# microGate.net
KiCad netlist of a schematic drawn in Altium Designer
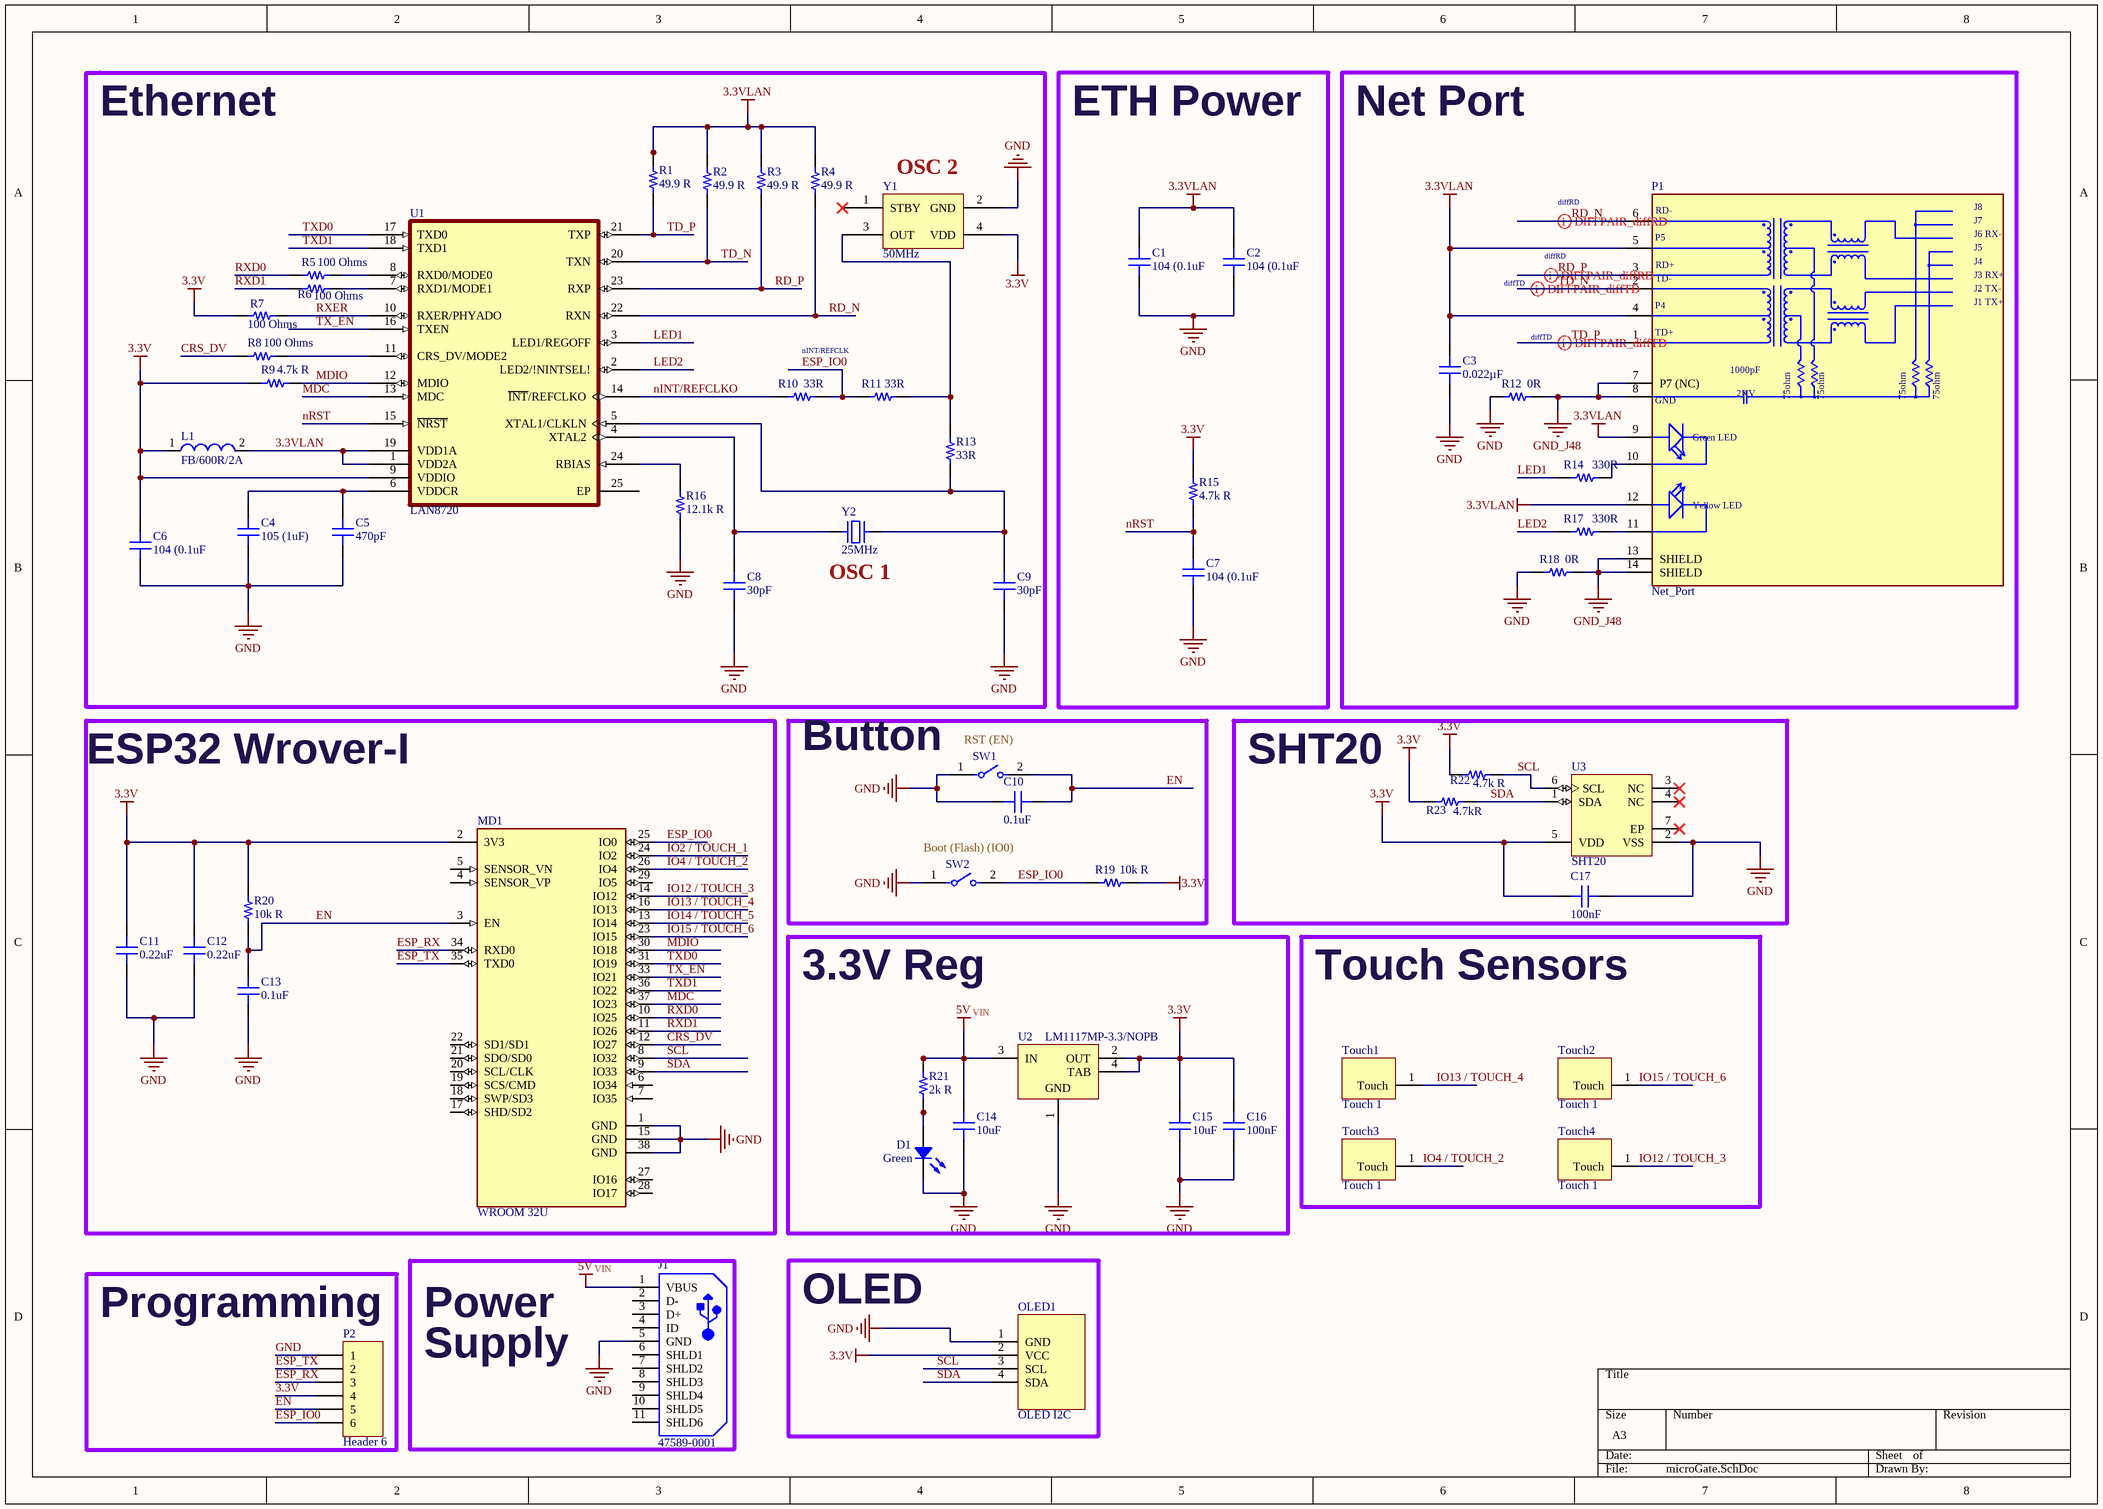
[diagram p0: microGate.SchDoc]

(export (version "E")
  (design (tool "Eeschema 10.0.6"))
  (components
    (comp (ref "C1")
      (value "104 (0.1uF")
      (footprint "CAP 0805_2012")
      (description "CAP CER SMD 0805 22PF 5% 50V X7R")
      (fields (field (name "PART NUMBER") "C0805C220J5RAC7800") (field (name "MANUFACTURER") "KEMET"))
      (libsource (lib "Celestial Altium Library - altium_library") (part "Capacitor"))
    )
    (comp (ref "C2")
      (value "104 (0.1uF")
      (footprint "CAP 0805_2012")
      (description "CAP CER SMD 0805 22PF 5% 50V X7R")
      (fields (field (name "PART NUMBER") "C0805C220J5RAC7800") (field (name "MANUFACTURER") "KEMET"))
      (libsource (lib "Celestial Altium Library - altium_library") (part "Capacitor"))
    )
    (comp (ref "C3")
      (value "0.022µF")
      (footprint "CAP 0805_2012")
      (description "CAP CER SMD 0805 22PF 5% 50V X7R")
      (fields (field (name "PART NUMBER") "C0805C220J5RAC7800") (field (name "MANUFACTURER") "KEMET"))
      (libsource (lib "Celestial Altium Library - altium_library") (part "Capacitor"))
    )
    (comp (ref "C4")
      (value "105 (1uF)")
      (footprint "CAP 0805_2012")
      (description "CAP CER SMD 0805 22PF 5% 50V X7R")
      (fields (field (name "PART NUMBER") "C0805C220J5RAC7800") (field (name "MANUFACTURER") "KEMET"))
      (libsource (lib "Celestial Altium Library - altium_library") (part "Capacitor"))
    )
    (comp (ref "C5")
      (value "470pF")
      (footprint "CAP 0805_2012")
      (description "CAP CER SMD 0805 22PF 5% 50V X7R")
      (fields (field (name "PART NUMBER") "C0805C220J5RAC7800") (field (name "MANUFACTURER") "KEMET"))
      (libsource (lib "Celestial Altium Library - altium_library") (part "Capacitor"))
    )
    (comp (ref "C6")
      (value "104 (0.1uF")
      (footprint "CAP 0805_2012")
      (description "CAP CER SMD 0805 22PF 5% 50V X7R")
      (fields (field (name "PART NUMBER") "C0805C220J5RAC7800") (field (name "MANUFACTURER") "KEMET"))
      (libsource (lib "Celestial Altium Library - altium_library") (part "Capacitor"))
    )
    (comp (ref "C7")
      (value "104 (0.1uF")
      (footprint "CAP 0805_2012")
      (description "CAP CER SMD 0805 22PF 5% 50V X7R")
      (fields (field (name "PART NUMBER") "C0805C220J5RAC7800") (field (name "MANUFACTURER") "KEMET"))
      (libsource (lib "Celestial Altium Library - altium_library") (part "Capacitor"))
    )
    (comp (ref "C8")
      (value "30pF")
      (footprint "CAP 0805_2012")
      (description "CAP CER SMD 0805 22PF 5% 50V X7R")
      (fields (field (name "PART NUMBER") "C0805C220J5RAC7800") (field (name "MANUFACTURER") "KEMET"))
      (libsource (lib "Celestial Altium Library - altium_library") (part "Capacitor"))
    )
    (comp (ref "C9")
      (value "30pF")
      (footprint "CAP 0805_2012")
      (description "CAP CER SMD 0805 22PF 5% 50V X7R")
      (fields (field (name "PART NUMBER") "C0805C220J5RAC7800") (field (name "MANUFACTURER") "KEMET"))
      (libsource (lib "Celestial Altium Library - altium_library") (part "Capacitor"))
    )
    (comp (ref "C10")
      (value "0.1uF")
      (footprint "CAP 0805_2012")
      (description "CAP CER SMD 0805 22PF 5% 50V X7R")
      (fields (field (name "PART NUMBER") "C0805C220J5RAC7800") (field (name "MANUFACTURER") "KEMET"))
      (libsource (lib "Celestial Altium Library - altium_library") (part "Capacitor"))
    )
    (comp (ref "C11")
      (value "0.22uF")
      (footprint "CAP 0805_2012")
      (description "CAP CER SMD 0805 22PF 5% 50V X7R")
      (fields (field (name "PART NUMBER") "C0805C220J5RAC7800") (field (name "MANUFACTURER") "KEMET"))
      (libsource (lib "Celestial Altium Library - altium_library") (part "Capacitor"))
    )
    (comp (ref "C12")
      (value "0.22uF")
      (footprint "CAP 0805_2012")
      (description "CAP CER SMD 0805 22PF 5% 50V X7R")
      (fields (field (name "PART NUMBER") "C0805C220J5RAC7800") (field (name "MANUFACTURER") "KEMET"))
      (libsource (lib "Celestial Altium Library - altium_library") (part "Capacitor"))
    )
    (comp (ref "C13")
      (value "0.1uF")
      (footprint "CAP 0805_2012")
      (description "CAP CER SMD 0805 22PF 5% 50V X7R")
      (fields (field (name "PART NUMBER") "C0805C220J5RAC7800") (field (name "MANUFACTURER") "KEMET"))
      (libsource (lib "Celestial Altium Library - altium_library") (part "Capacitor"))
    )
    (comp (ref "C14")
      (value "10uF")
      (footprint "CAP 0805_2012")
      (description "CAP CER SMD 0805 22PF 5% 50V X7R")
      (fields (field (name "PART NUMBER") "C0805C220J5RAC7800") (field (name "MANUFACTURER") "KEMET"))
      (libsource (lib "Celestial Altium Library - altium_library") (part "Capacitor"))
    )
    (comp (ref "C15")
      (value "10uF")
      (footprint "CAP 0805_2012")
      (description "CAP CER SMD 0805 22PF 5% 50V X7R")
      (fields (field (name "PART NUMBER") "C0805C220J5RAC7800") (field (name "MANUFACTURER") "KEMET"))
      (libsource (lib "Celestial Altium Library - altium_library") (part "Capacitor"))
    )
    (comp (ref "C16")
      (value "100nF")
      (footprint "CAP 0805_2012")
      (description "CAP CER SMD 0805 22PF 5% 50V X7R")
      (fields (field (name "PART NUMBER") "C0805C220J5RAC7800") (field (name "MANUFACTURER") "KEMET"))
      (libsource (lib "Celestial Altium Library - altium_library") (part "Capacitor"))
    )
    (comp (ref "C17")
      (value "100nF")
      (footprint "CAP 0805_2012")
      (description "CAP CER SMD 0805 22PF 5% 50V X7R")
      (fields (field (name "PART NUMBER") "C0805C220J5RAC7800") (field (name "MANUFACTURER") "KEMET"))
      (libsource (lib "Celestial Altium Library - altium_library") (part "Capacitor"))
    )
    (comp (ref "D1")
      (value "Green")
      (footprint "LED 0603_1608 GREEN")
      (description "LED GREEN DIFFUSED 1608 SMD")
      (fields (field (name "PART NUMBER") "BG1111C-TR") (field (name "MANUFACTURER") "Stanley Electric Co"))
      (libsource (lib "Celestial Altium Library - altium_library") (part "LED"))
    )
    (comp (ref "J1")
      (value "47589-0001")
      (footprint "MOLX-47589-0001_V")
      (description "Right Angle Female Type AB Micro USB Connector, 30 V, 1.8 A, -30 to 85 degC, RoHS, Tape and Reel")
      (fields (field (name "MANUFACTURER") "Molex"))
      (libsource (lib "Altium Content Vault") (part "USB-5-6SHLD"))
    )
    (comp (ref "L1")
      (value "FB/600R/2A")
      (footprint "SMD-0805")
      (description "İsmi : 742792040 SMD EMI Suppression Ferrite Bead WE-CBF, Z = 600 Ohm")
      (libsource (lib "Altium Content Vault") (part "PAS-IND-INDUCTOR-2"))
    )
    (comp (ref "MD1")
      (value "WROOM 32U")
      (footprint "ESP32 WROOM 32U")
      (libsource (lib "microGate") (part "ESP32 WROOM 32U"))
    )
    (comp (ref "OLED1")
      (value "OLED I2C")
      (footprint "OLED I2C")
      (libsource (lib "microGate") (part "OLED I2C"))
    )
    (comp (ref "P1")
      (value "Net_Port")
      (footprint "HR911105A")
      (libsource (lib "microGate") (part "HR911105A"))
    )
    (comp (ref "P2")
      (value "Header 6")
      (footprint "HDR1X6")
      (description "Header, 6-Pin")
      (fields (field (name "PUBLISHER") "Altium Limited"))
      (libsource (lib "Miscellaneous Connectors") (part "Header 6"))
    )
    (comp (ref "R1")
      (value "49.9 R")
      (footprint "RES 0805_2012")
      (description "RES, PULSE, 0805, 5%, 100 OHM, 0")
      (fields
        (field (name "PART NUMBER") "RPC0805JT100R-UP")
        (field (name "MANUFACTURER") "Stackpole Electronics Inc")
      )
      (libsource (lib "Celestial Altium Library - altium_library") (part "Resistor"))
    )
    (comp (ref "R2")
      (value "49.9 R")
      (footprint "RES 0805_2012")
      (description "RES, PULSE, 0805, 5%, 100 OHM, 0")
      (fields
        (field (name "PART NUMBER") "RPC0805JT100R-UP")
        (field (name "MANUFACTURER") "Stackpole Electronics Inc")
      )
      (libsource (lib "Celestial Altium Library - altium_library") (part "Resistor"))
    )
    (comp (ref "R3")
      (value "49.9 R")
      (footprint "RES 0805_2012")
      (description "RES, PULSE, 0805, 5%, 100 OHM, 0")
      (fields
        (field (name "PART NUMBER") "RPC0805JT100R-UP")
        (field (name "MANUFACTURER") "Stackpole Electronics Inc")
      )
      (libsource (lib "Celestial Altium Library - altium_library") (part "Resistor"))
    )
    (comp (ref "R4")
      (value "49.9 R")
      (footprint "RES 0805_2012")
      (description "RES, PULSE, 0805, 5%, 100 OHM, 0")
      (fields
        (field (name "PART NUMBER") "RPC0805JT100R-UP")
        (field (name "MANUFACTURER") "Stackpole Electronics Inc")
      )
      (libsource (lib "Celestial Altium Library - altium_library") (part "Resistor"))
    )
    (comp (ref "R5")
      (value "100 Ohms")
      (footprint "RES 0805_2012")
      (description "RES, PULSE, 0805, 5%, 100 OHM, 0")
      (fields
        (field (name "PART NUMBER") "RPC0805JT100R-UP")
        (field (name "MANUFACTURER") "Stackpole Electronics Inc")
      )
      (libsource (lib "Celestial Altium Library - altium_library") (part "Resistor"))
    )
    (comp (ref "R6")
      (value "100 Ohms")
      (footprint "RES 0805_2012")
      (description "RES, PULSE, 0805, 5%, 100 OHM, 0")
      (fields
        (field (name "PART NUMBER") "RPC0805JT100R-UP")
        (field (name "MANUFACTURER") "Stackpole Electronics Inc")
      )
      (libsource (lib "Celestial Altium Library - altium_library") (part "Resistor"))
    )
    (comp (ref "R7")
      (value "100 Ohms")
      (footprint "RES 0805_2012")
      (description "RES, PULSE, 0805, 5%, 100 OHM, 0")
      (fields
        (field (name "PART NUMBER") "RPC0805JT100R-UP")
        (field (name "MANUFACTURER") "Stackpole Electronics Inc")
      )
      (libsource (lib "Celestial Altium Library - altium_library") (part "Resistor"))
    )
    (comp (ref "R8")
      (value "100 Ohms")
      (footprint "RES 0805_2012")
      (description "RES, PULSE, 0805, 5%, 100 OHM, 0")
      (fields
        (field (name "PART NUMBER") "RPC0805JT100R-UP")
        (field (name "MANUFACTURER") "Stackpole Electronics Inc")
      )
      (libsource (lib "Celestial Altium Library - altium_library") (part "Resistor"))
    )
    (comp (ref "R9")
      (value "4.7k R")
      (footprint "RES 0805_2012")
      (description "RES, PULSE, 0805, 5%, 100 OHM, 0")
      (fields
        (field (name "PART NUMBER") "RPC0805JT100R-UP")
        (field (name "MANUFACTURER") "Stackpole Electronics Inc")
      )
      (libsource (lib "Celestial Altium Library - altium_library") (part "Resistor"))
    )
    (comp (ref "R10")
      (value "33R")
      (footprint "RES 0805_2012")
      (description "RES, PULSE, 0805, 5%, 100 OHM, 0")
      (fields
        (field (name "PART NUMBER") "RPC0805JT100R-UP")
        (field (name "MANUFACTURER") "Stackpole Electronics Inc")
      )
      (libsource (lib "Celestial Altium Library - altium_library") (part "Resistor"))
    )
    (comp (ref "R11")
      (value "33R")
      (footprint "RES 0805_2012")
      (description "RES, PULSE, 0805, 5%, 100 OHM, 0")
      (fields
        (field (name "PART NUMBER") "RPC0805JT100R-UP")
        (field (name "MANUFACTURER") "Stackpole Electronics Inc")
      )
      (libsource (lib "Celestial Altium Library - altium_library") (part "Resistor"))
    )
    (comp (ref "R12")
      (value "0R")
      (footprint "RES 0805_2012")
      (description "RES, PULSE, 0805, 5%, 100 OHM, 0")
      (fields
        (field (name "PART NUMBER") "RPC0805JT100R-UP")
        (field (name "MANUFACTURER") "Stackpole Electronics Inc")
      )
      (libsource (lib "Celestial Altium Library - altium_library") (part "Resistor"))
    )
    (comp (ref "R13")
      (value "33R")
      (footprint "RES 0805_2012")
      (description "RES, PULSE, 0805, 5%, 100 OHM, 0")
      (fields
        (field (name "PART NUMBER") "RPC0805JT100R-UP")
        (field (name "MANUFACTURER") "Stackpole Electronics Inc")
      )
      (libsource (lib "Celestial Altium Library - altium_library") (part "Resistor"))
    )
    (comp (ref "R14")
      (value "330R")
      (footprint "RES 0805_2012")
      (description "RES, PULSE, 0805, 5%, 100 OHM, 0")
      (fields
        (field (name "PART NUMBER") "RPC0805JT100R-UP")
        (field (name "MANUFACTURER") "Stackpole Electronics Inc")
      )
      (libsource (lib "Celestial Altium Library - altium_library") (part "Resistor"))
    )
    (comp (ref "R15")
      (value "4.7k R")
      (footprint "RES 0805_2012")
      (description "RES, PULSE, 0805, 5%, 100 OHM, 0")
      (fields
        (field (name "PART NUMBER") "RPC0805JT100R-UP")
        (field (name "MANUFACTURER") "Stackpole Electronics Inc")
      )
      (libsource (lib "Celestial Altium Library - altium_library") (part "Resistor"))
    )
    (comp (ref "R16")
      (value "12.1k R")
      (footprint "RES 0805_2012")
      (description "RES, PULSE, 0805, 5%, 100 OHM, 0")
      (fields
        (field (name "PART NUMBER") "RPC0805JT100R-UP")
        (field (name "MANUFACTURER") "Stackpole Electronics Inc")
      )
      (libsource (lib "Celestial Altium Library - altium_library") (part "Resistor"))
    )
    (comp (ref "R17")
      (value "330R")
      (footprint "RES 0805_2012")
      (description "RES, PULSE, 0805, 5%, 100 OHM, 0")
      (fields
        (field (name "PART NUMBER") "RPC0805JT100R-UP")
        (field (name "MANUFACTURER") "Stackpole Electronics Inc")
      )
      (libsource (lib "Celestial Altium Library - altium_library") (part "Resistor"))
    )
    (comp (ref "R18")
      (value "0R")
      (footprint "RES 0805_2012")
      (description "RES, PULSE, 0805, 5%, 100 OHM, 0")
      (fields
        (field (name "PART NUMBER") "RPC0805JT100R-UP")
        (field (name "MANUFACTURER") "Stackpole Electronics Inc")
      )
      (libsource (lib "Celestial Altium Library - altium_library") (part "Resistor"))
    )
    (comp (ref "R19")
      (value "10k R")
      (footprint "RES 0805_2012")
      (description "RES, PULSE, 0805, 5%, 100 OHM, 0")
      (fields
        (field (name "PART NUMBER") "RPC0805JT100R-UP")
        (field (name "MANUFACTURER") "Stackpole Electronics Inc")
      )
      (libsource (lib "Celestial Altium Library - altium_library") (part "Resistor"))
    )
    (comp (ref "R20")
      (value "10k R")
      (footprint "RES 0805_2012")
      (description "RES, PULSE, 0805, 5%, 100 OHM, 0")
      (fields
        (field (name "PART NUMBER") "RPC0805JT100R-UP")
        (field (name "MANUFACTURER") "Stackpole Electronics Inc")
      )
      (libsource (lib "Celestial Altium Library - altium_library") (part "Resistor"))
    )
    (comp (ref "R21")
      (value "2k R")
      (footprint "RES 0805_2012")
      (description "RES, PULSE, 0805, 5%, 100 OHM, 0")
      (fields
        (field (name "PART NUMBER") "RPC0805JT100R-UP")
        (field (name "MANUFACTURER") "Stackpole Electronics Inc")
      )
      (libsource (lib "Celestial Altium Library - altium_library") (part "Resistor"))
    )
    (comp (ref "R22")
      (value "4.7k R")
      (footprint "RES 0805_2012")
      (description "RES, PULSE, 0805, 5%, 100 OHM, 0")
      (fields
        (field (name "PART NUMBER") "RPC0805JT100R-UP")
        (field (name "MANUFACTURER") "Stackpole Electronics Inc")
      )
      (libsource (lib "Celestial Altium Library - altium_library") (part "Resistor"))
    )
    (comp (ref "R23")
      (value "4.7kR")
      (footprint "RES 0805_2012")
      (description "RES, PULSE, 0805, 5%, 100 OHM, 0")
      (fields
        (field (name "PART NUMBER") "RPC0805JT100R-UP")
        (field (name "MANUFACTURER") "Stackpole Electronics Inc")
      )
      (libsource (lib "Celestial Altium Library - altium_library") (part "Resistor"))
    )
    (comp (ref "SW1")
      (value "~")
      (footprint "FP-B3U-1000P-B-MFG")
      (description "SWITCH TACTILE SPST-NO 0.05A 12V")
      (fields
        (field (name "MANUFACTURER PART NUMBER") "B3U-1000P-B")
        (field (name "OCTOPART") "https://octopart.com/b3u-1000p-b-omron-1057356")
      )
      (libsource (lib "Altium Content Vault") (part "bb27bde45df87f1f469753f287ef5ae"))
    )
    (comp (ref "SW2")
      (value "~")
      (footprint "FP-B3U-1000P-B-MFG")
      (description "SWITCH TACTILE SPST-NO 0.05A 12V")
      (fields
        (field (name "MANUFACTURER PART NUMBER") "B3U-1000P-B")
        (field (name "OCTOPART") "https://octopart.com/b3u-1000p-b-omron-1057356")
      )
      (libsource (lib "Altium Content Vault") (part "bb27bde45df87f1f469753f287ef5ae"))
    )
    (comp (ref "Touch1") (value "Touch 1") (footprint "Touch") (libsource (lib "microGate") (part "Touch 1")))
    (comp (ref "Touch2") (value "Touch 1") (footprint "Touch") (libsource (lib "microGate") (part "Touch 1")))
    (comp (ref "Touch3") (value "Touch 1") (footprint "Touch") (libsource (lib "microGate") (part "Touch 1")))
    (comp (ref "Touch4") (value "Touch 1") (footprint "Touch") (libsource (lib "microGate") (part "Touch 1")))
    (comp (ref "U1")
      (value "LAN8720")
      (footprint "LAN8720 FOOT")
      (libsource (lib "microGate") (part "LAN8720"))
    )
    (comp (ref "U2")
      (value "LM1117MP-3.3/NOPB")
      (footprint "DCY0004A_L")
      (description "800mA Low-Dropout Linear Regulator, 4-pin SOT-223, Pb-Free")
      (fields (field (name "MANUFACTURER") "Texas Instruments"))
      (libsource (lib "Altium Content Vault") (part "PM-REG-LM1086-SOT4"))
    )
    (comp (ref "U3")
      (value "SHT20")
      (footprint "SENS-SHT2X-6_V")
      (description "Humidity and Temperature Sensor IC, 2.1 to 3.6 V, -40 to 125 degC, 6-Pin DFN, RoHS, Tape and Reel")
      (fields (field (name "MANUFACTURER") "Sensirion-AG"))
      (libsource (lib "Altium Content Vault") (part "SENS-SHT20-6"))
    )
    (comp (ref "Y1")
      (value "50MHz")
      (footprint "ABRACON ASDMB")
      (description "MEMS OSC XO 50.0000MHZ LVCMOS")
      (fields (field (name "PART NUMBER") "ASDMB-50.000MHZ-EC-T") (field (name "MANUFACTURER") "Abracon LLC"))
      (libsource (lib "Celestial Altium Library - altium_library") (part "Abracon MEMS ASDMB"))
    )
    (comp (ref "Y2")
      (value "25MHz")
      (footprint "ABRACON ABLS")
      (description "CRYSTAL 25.000MHZ 18PF SMD")
      (fields (field (name "PART NUMBER") "ABLS-25.000MHZ-D-FT") (field (name "MANUFACTURER") "Abracon LLC"))
      (libsource (lib "Celestial Altium Library - altium_library") (part "Abracon Crystal ABLS"))
    )
  )
  (nets
    (net (code "1") (name "/CRS_DV") (class "Default")
      (node (ref "MD1") (pin "12") (pinfunction "IO27_12") (pintype "bidirectional"))
      (node (ref "R8") (pin "1") (pinfunction "1_1") (pintype "passive"))
    )
    (net (code "2") (name "/EN") (class "Default")
      (node (ref "C10") (pin "2") (pinfunction "2_2") (pintype "passive"))
      (node (ref "C13") (pin "2") (pinfunction "2_2") (pintype "passive"))
      (node (ref "MD1") (pin "3") (pinfunction "EN_3") (pintype "input"))
      (node (ref "P2") (pin "5") (pinfunction "5_5") (pintype "passive"))
      (node (ref "R20") (pin "1") (pinfunction "1_1") (pintype "passive"))
      (node (ref "SW1") (pin "2") (pinfunction "2_2") (pintype "passive"))
    )
    (net (code "3") (name "/ESP_IO0") (class "Default")
      (node (ref "MD1") (pin "25") (pinfunction "IO0_25") (pintype "bidirectional"))
      (node (ref "P2") (pin "6") (pinfunction "6_6") (pintype "passive"))
      (node (ref "R10") (pin "2") (pinfunction "2_2") (pintype "passive"))
      (node (ref "R11") (pin "1") (pinfunction "1_1") (pintype "passive"))
      (node (ref "R19") (pin "1") (pinfunction "1_1") (pintype "passive"))
      (node (ref "SW2") (pin "2") (pinfunction "2_2") (pintype "passive"))
    )
    (net (code "4") (name "/ESP_RX") (class "Default")
      (node (ref "MD1") (pin "34") (pinfunction "RXD0_34") (pintype "bidirectional"))
      (node (ref "P2") (pin "3") (pinfunction "3_3") (pintype "passive"))
    )
    (net (code "5") (name "/ESP_TX") (class "Default")
      (node (ref "MD1") (pin "35") (pinfunction "TXD0_35") (pintype "bidirectional"))
      (node (ref "P2") (pin "2") (pinfunction "2_2") (pintype "passive"))
    )
    (net (code "6") (name "/IO2 {slash} TOUCH_1") (class "Default")
      (node (ref "MD1") (pin "24") (pinfunction "IO2_24") (pintype "bidirectional"))
    )
    (net (code "7") (name "/IO4 {slash} TOUCH_2") (class "Default")
      (node (ref "MD1") (pin "26") (pinfunction "IO4_26") (pintype "bidirectional"))
      (node (ref "Touch3") (pin "1") (pinfunction "Touch_1") (pintype "passive"))
    )
    (net (code "8") (name "/IO12 {slash} TOUCH_3") (class "Default")
      (node (ref "MD1") (pin "14") (pinfunction "IO12_14") (pintype "bidirectional"))
      (node (ref "Touch4") (pin "1") (pinfunction "Touch_1") (pintype "passive"))
    )
    (net (code "9") (name "/IO13 {slash} TOUCH_4") (class "Default")
      (node (ref "MD1") (pin "16") (pinfunction "IO13_16") (pintype "bidirectional"))
      (node (ref "Touch1") (pin "1") (pinfunction "Touch_1") (pintype "passive"))
    )
    (net (code "10") (name "/IO14 {slash} TOUCH_5") (class "Default")
      (node (ref "MD1") (pin "13") (pinfunction "IO14_13") (pintype "bidirectional"))
    )
    (net (code "11") (name "/IO15 {slash} TOUCH_6") (class "Default")
      (node (ref "MD1") (pin "23") (pinfunction "IO15_23") (pintype "bidirectional"))
      (node (ref "Touch2") (pin "1") (pinfunction "Touch_1") (pintype "passive"))
    )
    (net (code "12") (name "/LED1") (class "Default")
      (node (ref "R14") (pin "1") (pinfunction "1_1") (pintype "passive"))
      (node (ref "U1") (pin "3") (pinfunction "LED1/REGOFF_3") (pintype "bidirectional"))
    )
    (net (code "13") (name "/LED2") (class "Default")
      (node (ref "R17") (pin "1") (pinfunction "1_1") (pintype "passive"))
      (node (ref "U1") (pin "2") (pinfunction "LED2/!NINTSEL!_2") (pintype "bidirectional"))
    )
    (net (code "14") (name "/MDC") (class "Default")
      (node (ref "MD1") (pin "37") (pinfunction "IO23_37") (pintype "bidirectional"))
      (node (ref "U1") (pin "13") (pinfunction "MDC_13") (pintype "input"))
    )
    (net (code "15") (name "/MDIO") (class "Default")
      (node (ref "MD1") (pin "30") (pinfunction "IO18_30") (pintype "bidirectional"))
      (node (ref "R9") (pin "2") (pinfunction "2_2") (pintype "passive"))
      (node (ref "U1") (pin "12") (pinfunction "MDIO_12") (pintype "bidirectional"))
    )
    (net (code "16") (name "/RD_N") (class "Default")
      (node (ref "P1") (pin "6") (pinfunction "RD-_6") (pintype "passive"))
      (node (ref "R4") (pin "1") (pinfunction "1_1") (pintype "passive"))
      (node (ref "U1") (pin "22") (pinfunction "RXN_22") (pintype "bidirectional"))
    )
    (net (code "17") (name "/RD_P") (class "Default")
      (node (ref "P1") (pin "3") (pinfunction "RD+_3") (pintype "passive"))
      (node (ref "R3") (pin "1") (pinfunction "1_1") (pintype "passive"))
      (node (ref "U1") (pin "23") (pinfunction "RXP_23") (pintype "bidirectional"))
    )
    (net (code "18") (name "/RXD0") (class "Default")
      (node (ref "MD1") (pin "10") (pinfunction "IO25_10") (pintype "bidirectional"))
      (node (ref "R5") (pin "1") (pinfunction "1_1") (pintype "passive"))
    )
    (net (code "19") (name "/RXD1") (class "Default")
      (node (ref "MD1") (pin "11") (pinfunction "IO26_11") (pintype "bidirectional"))
      (node (ref "R6") (pin "1") (pinfunction "1_1") (pintype "passive"))
    )
    (net (code "20") (name "/RXER") (class "Default")
      (node (ref "R7") (pin "2") (pinfunction "2_2") (pintype "passive"))
      (node (ref "U1") (pin "10") (pinfunction "RXER/PHYADO_10") (pintype "bidirectional"))
    )
    (net (code "21") (name "/SCL") (class "Default")
      (node (ref "MD1") (pin "8") (pinfunction "IO32_8") (pintype "bidirectional"))
      (node (ref "OLED1") (pin "3") (pinfunction "SCL_3") (pintype "passive"))
      (node (ref "R22") (pin "2") (pinfunction "2_2") (pintype "passive"))
      (node (ref "U3") (pin "6") (pinfunction "SCL_6") (pintype "bidirectional"))
    )
    (net (code "22") (name "/SDA") (class "Default")
      (node (ref "MD1") (pin "9") (pinfunction "IO33_9") (pintype "bidirectional"))
      (node (ref "OLED1") (pin "4") (pinfunction "SDA_4") (pintype "passive"))
      (node (ref "R23") (pin "2") (pinfunction "2_2") (pintype "passive"))
      (node (ref "U3") (pin "1") (pinfunction "SDA_1") (pintype "bidirectional"))
    )
    (net (code "23") (name "/TD_N") (class "Default")
      (node (ref "P1") (pin "2") (pinfunction "TD-_2") (pintype "passive"))
      (node (ref "R2") (pin "1") (pinfunction "1_1") (pintype "passive"))
      (node (ref "U1") (pin "20") (pinfunction "TXN_20") (pintype "bidirectional"))
    )
    (net (code "24") (name "/TD_P") (class "Default")
      (node (ref "P1") (pin "1") (pinfunction "TD+_1") (pintype "passive"))
      (node (ref "R1") (pin "1") (pinfunction "1_1") (pintype "passive"))
      (node (ref "U1") (pin "21") (pinfunction "TXP_21") (pintype "bidirectional"))
    )
    (net (code "25") (name "/TXD0") (class "Default")
      (node (ref "MD1") (pin "31") (pinfunction "IO19_31") (pintype "bidirectional"))
      (node (ref "U1") (pin "17") (pinfunction "TXD0_17") (pintype "input"))
    )
    (net (code "26") (name "/TXD1") (class "Default")
      (node (ref "MD1") (pin "36") (pinfunction "IO22_36") (pintype "bidirectional"))
      (node (ref "U1") (pin "18") (pinfunction "TXD1_18") (pintype "input"))
    )
    (net (code "27") (name "/TX_EN") (class "Default")
      (node (ref "MD1") (pin "33") (pinfunction "IO21_33") (pintype "bidirectional"))
      (node (ref "U1") (pin "16") (pinfunction "TXEN_16") (pintype "input"))
    )
    (net (code "28") (name "/nINT{slash}REFCLKO") (class "Default")
      (node (ref "R10") (pin "1") (pinfunction "1_1") (pintype "passive"))
      (node (ref "U1") (pin "14") (pinfunction "~{INT}/REFCLKO_14") (pintype "output"))
    )
    (net (code "29") (name "/nRST") (class "Default")
      (node (ref "C7") (pin "2") (pinfunction "2_2") (pintype "passive"))
      (node (ref "R15") (pin "1") (pinfunction "1_1") (pintype "passive"))
      (node (ref "U1") (pin "15") (pinfunction "~{NRST}_15") (pintype "input"))
    )
    (net (code "30") (name "3.3V") (class "Default")
      (node (ref "C11") (pin "2") (pinfunction "2_2") (pintype "passive"))
      (node (ref "C12") (pin "2") (pinfunction "2_2") (pintype "passive"))
      (node (ref "C15") (pin "2") (pinfunction "2_2") (pintype "passive"))
      (node (ref "C16") (pin "2") (pinfunction "2_2") (pintype "passive"))
      (node (ref "C17") (pin "1") (pinfunction "1_1") (pintype "passive"))
      (node (ref "C6") (pin "2") (pinfunction "2_2") (pintype "passive"))
      (node (ref "L1") (pin "1") (pinfunction "1_1") (pintype "passive"))
      (node (ref "MD1") (pin "2") (pinfunction "3V3_2") (pintype "power_in"))
      (node (ref "OLED1") (pin "2") (pinfunction "VCC_2") (pintype "passive"))
      (node (ref "P2") (pin "4") (pinfunction "4_4") (pintype "passive"))
      (node (ref "R15") (pin "2") (pinfunction "2_2") (pintype "passive"))
      (node (ref "R19") (pin "2") (pinfunction "2_2") (pintype "passive"))
      (node (ref "R20") (pin "2") (pinfunction "2_2") (pintype "passive"))
      (node (ref "R22") (pin "1") (pinfunction "1_1") (pintype "passive"))
      (node (ref "R23") (pin "1") (pinfunction "1_1") (pintype "passive"))
      (node (ref "R7") (pin "1") (pinfunction "1_1") (pintype "passive"))
      (node (ref "R9") (pin "1") (pinfunction "1_1") (pintype "passive"))
      (node (ref "U1") (pin "9") (pinfunction "VDDIO_9") (pintype "power_in"))
      (node (ref "U2") (pin "2") (pinfunction "OUT_2") (pintype "power_in"))
      (node (ref "U2") (pin "4") (pinfunction "TAB_4") (pintype "power_in"))
      (node (ref "U3") (pin "5") (pinfunction "VDD_5") (pintype "power_in"))
      (node (ref "Y1") (pin "4") (pinfunction "VDD_4") (pintype "passive"))
    )
    (net (code "31") (name "3.3VLAN") (class "Default")
      (node (ref "C1") (pin "2") (pinfunction "2_2") (pintype "passive"))
      (node (ref "C2") (pin "2") (pinfunction "2_2") (pintype "passive"))
      (node (ref "C3") (pin "2") (pinfunction "2_2") (pintype "passive"))
      (node (ref "L1") (pin "2") (pinfunction "2_2") (pintype "passive"))
      (node (ref "P1") (pin "12") (pinfunction "YA_12") (pintype "passive"))
      (node (ref "P1") (pin "4") (pinfunction "P4_4") (pintype "passive"))
      (node (ref "P1") (pin "5") (pinfunction "P5_5") (pintype "passive"))
      (node (ref "P1") (pin "9") (pinfunction "GA_9") (pintype "passive"))
      (node (ref "R1") (pin "2") (pinfunction "2_2") (pintype "passive"))
      (node (ref "R2") (pin "2") (pinfunction "2_2") (pintype "passive"))
      (node (ref "R3") (pin "2") (pinfunction "2_2") (pintype "passive"))
      (node (ref "R4") (pin "2") (pinfunction "2_2") (pintype "passive"))
      (node (ref "U1") (pin "1") (pinfunction "VDD2A_1") (pintype "power_in"))
      (node (ref "U1") (pin "19") (pinfunction "VDD1A_19") (pintype "power_in"))
    )
    (net (code "32") (name "5V") (class "Default")
      (node (ref "C14") (pin "2") (pinfunction "2_2") (pintype "passive"))
      (node (ref "J1") (pin "1") (pinfunction "VBUS_1") (pintype "passive"))
      (node (ref "R21") (pin "2") (pinfunction "2_2") (pintype "passive"))
      (node (ref "U2") (pin "3") (pinfunction "IN_3") (pintype "power_in"))
    )
    (net (code "33") (name "GND") (class "Default")
      (node (ref "C1") (pin "1") (pinfunction "1_1") (pintype "passive"))
      (node (ref "C10") (pin "1") (pinfunction "1_1") (pintype "passive"))
      (node (ref "C11") (pin "1") (pinfunction "1_1") (pintype "passive"))
      (node (ref "C12") (pin "1") (pinfunction "1_1") (pintype "passive"))
      (node (ref "C13") (pin "1") (pinfunction "1_1") (pintype "passive"))
      (node (ref "C14") (pin "1") (pinfunction "1_1") (pintype "passive"))
      (node (ref "C15") (pin "1") (pinfunction "1_1") (pintype "passive"))
      (node (ref "C16") (pin "1") (pinfunction "1_1") (pintype "passive"))
      (node (ref "C17") (pin "2") (pinfunction "2_2") (pintype "passive"))
      (node (ref "C2") (pin "1") (pinfunction "1_1") (pintype "passive"))
      (node (ref "C3") (pin "1") (pinfunction "1_1") (pintype "passive"))
      (node (ref "C4") (pin "1") (pinfunction "1_1") (pintype "passive"))
      (node (ref "C5") (pin "1") (pinfunction "1_1") (pintype "passive"))
      (node (ref "C6") (pin "1") (pinfunction "1_1") (pintype "passive"))
      (node (ref "C7") (pin "1") (pinfunction "1_1") (pintype "passive"))
      (node (ref "C8") (pin "1") (pinfunction "1_1") (pintype "passive"))
      (node (ref "C9") (pin "1") (pinfunction "1_1") (pintype "passive"))
      (node (ref "D1") (pin "2") (pinfunction "2_2") (pintype "passive"))
      (node (ref "J1") (pin "5") (pinfunction "GND_5") (pintype "passive"))
      (node (ref "MD1") (pin "1") (pinfunction "GND_1") (pintype "power_in"))
      (node (ref "MD1") (pin "15") (pinfunction "GND_15") (pintype "power_in"))
      (node (ref "MD1") (pin "38") (pinfunction "GND_38") (pintype "power_in"))
      (node (ref "OLED1") (pin "1") (pinfunction "GND_1") (pintype "passive"))
      (node (ref "P2") (pin "1") (pinfunction "1_1") (pintype "passive"))
      (node (ref "R12") (pin "1") (pinfunction "1_1") (pintype "passive"))
      (node (ref "R16") (pin "1") (pinfunction "1_1") (pintype "passive"))
      (node (ref "R18") (pin "1") (pinfunction "1_1") (pintype "passive"))
      (node (ref "SW1") (pin "1") (pinfunction "1_1") (pintype "passive"))
      (node (ref "SW2") (pin "1") (pinfunction "1_1") (pintype "passive"))
      (node (ref "U2") (pin "1") (pinfunction "GND_1") (pintype "power_in"))
      (node (ref "U3") (pin "2") (pinfunction "VSS_2") (pintype "power_in"))
      (node (ref "Y1") (pin "2") (pinfunction "GND_2") (pintype "passive"))
    )
    (net (code "34") (name "GND_J48") (class "Default")
      (node (ref "P1") (pin "13") (pinfunction "SHIELD_13") (pintype "passive"))
      (node (ref "P1") (pin "14") (pinfunction "SHIELD_14") (pintype "passive"))
      (node (ref "P1") (pin "7") (pinfunction "P7_(NC)_7") (pintype "passive"))
      (node (ref "P1") (pin "8") (pinfunction "GND_8") (pintype "power_in"))
      (node (ref "R12") (pin "2") (pinfunction "2_2") (pintype "passive"))
      (node (ref "R18") (pin "2") (pinfunction "2_2") (pintype "passive"))
    )
    (net (code "35") (name "Net-(D1-Pad1)") (class "Default")
      (node (ref "D1") (pin "1") (pinfunction "1_1") (pintype "passive"))
      (node (ref "R21") (pin "1") (pinfunction "1_1") (pintype "passive"))
    )
    (net (code "36") (name "Net-(P1-GC)") (class "Default")
      (node (ref "P1") (pin "10") (pinfunction "GC_10") (pintype "passive"))
      (node (ref "R14") (pin "2") (pinfunction "2_2") (pintype "passive"))
    )
    (net (code "37") (name "Net-(P1-YC)") (class "Default")
      (node (ref "P1") (pin "11") (pinfunction "YC_11") (pintype "passive"))
      (node (ref "R17") (pin "2") (pinfunction "2_2") (pintype "passive"))
    )
    (net (code "38") (name "Net-(U1-CRS_DV{slash}MODE2)") (class "Default")
      (node (ref "R8") (pin "2") (pinfunction "2_2") (pintype "passive"))
      (node (ref "U1") (pin "11") (pinfunction "CRS_DV/MODE2_11") (pintype "bidirectional"))
    )
    (net (code "39") (name "Net-(U1-RBIAS)") (class "Default")
      (node (ref "R16") (pin "2") (pinfunction "2_2") (pintype "passive"))
      (node (ref "U1") (pin "24") (pinfunction "RBIAS_24") (pintype "input"))
    )
    (net (code "40") (name "Net-(U1-RXD0{slash}MODE0)") (class "Default")
      (node (ref "R5") (pin "2") (pinfunction "2_2") (pintype "passive"))
      (node (ref "U1") (pin "8") (pinfunction "RXD0/MODE0_8") (pintype "bidirectional"))
    )
    (net (code "41") (name "Net-(U1-RXD1{slash}MODE1)") (class "Default")
      (node (ref "R6") (pin "2") (pinfunction "2_2") (pintype "passive"))
      (node (ref "U1") (pin "7") (pinfunction "RXD1/MODE1_7") (pintype "bidirectional"))
    )
    (net (code "42") (name "Net-(U1-VDDCR)") (class "Default")
      (node (ref "C4") (pin "2") (pinfunction "2_2") (pintype "passive"))
      (node (ref "C5") (pin "2") (pinfunction "2_2") (pintype "passive"))
      (node (ref "U1") (pin "6") (pinfunction "VDDCR_6") (pintype "power_in"))
    )
    (net (code "43") (name "Net-(U1-XTAL1{slash}CLKLN)") (class "Default")
      (node (ref "C9") (pin "2") (pinfunction "2_2") (pintype "passive"))
      (node (ref "R13") (pin "1") (pinfunction "1_1") (pintype "passive"))
      (node (ref "U1") (pin "5") (pinfunction "XTAL1/CLKLN_5") (pintype "input"))
      (node (ref "Y2") (pin "2") (pinfunction "2_2") (pintype "passive"))
    )
    (net (code "44") (name "Net-(U1-XTAL2)") (class "Default")
      (node (ref "C8") (pin "2") (pinfunction "2_2") (pintype "passive"))
      (node (ref "U1") (pin "4") (pinfunction "XTAL2_4") (pintype "output"))
      (node (ref "Y2") (pin "1") (pinfunction "1_1") (pintype "passive"))
    )
    (net (code "45") (name "Net-(Y1-OUT)") (class "Default")
      (node (ref "R11") (pin "2") (pinfunction "2_2") (pintype "passive"))
      (node (ref "R13") (pin "2") (pinfunction "2_2") (pintype "passive"))
      (node (ref "Y1") (pin "3") (pinfunction "OUT_3") (pintype "passive"))
    )
    (net (code "46") (name "unconnected-(J1-D+-Pad3)") (class "Default")
      (node (ref "J1") (pin "3") (pinfunction "D+_3") (pintype "passive"))
    )
    (net (code "47") (name "unconnected-(J1-D--Pad2)") (class "Default")
      (node (ref "J1") (pin "2") (pinfunction "D-_2") (pintype "passive"))
    )
    (net (code "48") (name "unconnected-(J1-ID-Pad4)") (class "Default")
      (node (ref "J1") (pin "4") (pinfunction "ID_4") (pintype "passive"))
    )
    (net (code "49") (name "unconnected-(J1-SHLD1-Pad6)") (class "Default")
      (node (ref "J1") (pin "6") (pinfunction "SHLD1_6") (pintype "passive"))
    )
    (net (code "50") (name "unconnected-(J1-SHLD2-Pad7)") (class "Default")
      (node (ref "J1") (pin "7") (pinfunction "SHLD2_7") (pintype "passive"))
    )
    (net (code "51") (name "unconnected-(J1-SHLD3-Pad8)") (class "Default")
      (node (ref "J1") (pin "8") (pinfunction "SHLD3_8") (pintype "passive"))
    )
    (net (code "52") (name "unconnected-(J1-SHLD4-Pad9)") (class "Default")
      (node (ref "J1") (pin "9") (pinfunction "SHLD4_9") (pintype "passive"))
    )
    (net (code "53") (name "unconnected-(J1-SHLD5-Pad10)") (class "Default")
      (node (ref "J1") (pin "10") (pinfunction "SHLD5_10") (pintype "passive"))
    )
    (net (code "54") (name "unconnected-(J1-SHLD6-Pad11)") (class "Default")
      (node (ref "J1") (pin "11") (pinfunction "SHLD6_11") (pintype "passive"))
    )
    (net (code "55") (name "unconnected-(MD1-IO5-Pad29)") (class "Default")
      (node (ref "MD1") (pin "29") (pinfunction "IO5_29") (pintype "bidirectional"))
    )
    (net (code "56") (name "unconnected-(MD1-IO16-Pad27)") (class "Default")
      (node (ref "MD1") (pin "27") (pinfunction "IO16_27") (pintype "bidirectional"))
    )
    (net (code "57") (name "unconnected-(MD1-IO17-Pad28)") (class "Default")
      (node (ref "MD1") (pin "28") (pinfunction "IO17_28") (pintype "bidirectional"))
    )
    (net (code "58") (name "unconnected-(MD1-IO34-Pad6)") (class "Default")
      (node (ref "MD1") (pin "6") (pinfunction "IO34_6") (pintype "input"))
    )
    (net (code "59") (name "unconnected-(MD1-IO35-Pad7)") (class "Default")
      (node (ref "MD1") (pin "7") (pinfunction "IO35_7") (pintype "input"))
    )
    (net (code "60") (name "unconnected-(MD1-SCL{slash}CLK-Pad20)") (class "Default")
      (node (ref "MD1") (pin "20") (pinfunction "SCL/CLK_20") (pintype "bidirectional"))
    )
    (net (code "61") (name "unconnected-(MD1-SCS{slash}CMD-Pad19)") (class "Default")
      (node (ref "MD1") (pin "19") (pinfunction "SCS/CMD_19") (pintype "bidirectional"))
    )
    (net (code "62") (name "unconnected-(MD1-SD1{slash}SD1-Pad22)") (class "Default")
      (node (ref "MD1") (pin "22") (pinfunction "SD1/SD1_22") (pintype "bidirectional"))
    )
    (net (code "63") (name "unconnected-(MD1-SDO{slash}SD0-Pad21)") (class "Default")
      (node (ref "MD1") (pin "21") (pinfunction "SDO/SD0_21") (pintype "bidirectional"))
    )
    (net (code "64") (name "unconnected-(MD1-SENSOR_VN-Pad5)") (class "Default")
      (node (ref "MD1") (pin "5") (pinfunction "SENSOR_VN_5") (pintype "input"))
    )
    (net (code "65") (name "unconnected-(MD1-SENSOR_VP-Pad4)") (class "Default")
      (node (ref "MD1") (pin "4") (pinfunction "SENSOR_VP_4") (pintype "input"))
    )
    (net (code "66") (name "unconnected-(MD1-SHD{slash}SD2-Pad17)") (class "Default")
      (node (ref "MD1") (pin "17") (pinfunction "SHD/SD2_17") (pintype "bidirectional"))
    )
    (net (code "67") (name "unconnected-(MD1-SWP{slash}SD3-Pad18)") (class "Default")
      (node (ref "MD1") (pin "18") (pinfunction "SWP/SD3_18") (pintype "bidirectional"))
    )
    (net (code "68") (name "unconnected-(U1-EP-Pad25)") (class "Default")
      (node (ref "U1") (pin "25") (pinfunction "EP_25") (pintype "power_in"))
    )
    (net (code "69") (name "unconnected-(U3-EP-Pad7)") (class "Default")
      (node (ref "U3") (pin "7") (pinfunction "EP_7") (pintype "power_in+no_connect"))
    )
    (net (code "70") (name "unconnected-(U3-NC-Pad3)") (class "Default")
      (node (ref "U3") (pin "3") (pinfunction "NC_3") (pintype "passive+no_connect"))
    )
    (net (code "71") (name "unconnected-(U3-NC-Pad4)") (class "Default")
      (node (ref "U3") (pin "4") (pinfunction "NC_4") (pintype "passive+no_connect"))
    )
    (net (code "72") (name "unconnected-(Y1-STBY-Pad1)") (class "Default")
      (node (ref "Y1") (pin "1") (pinfunction "STBY_1") (pintype "passive+no_connect"))
    )
  )
)
